# Sheet4.net
KiCad netlist of a schematic drawn in Altium Designer
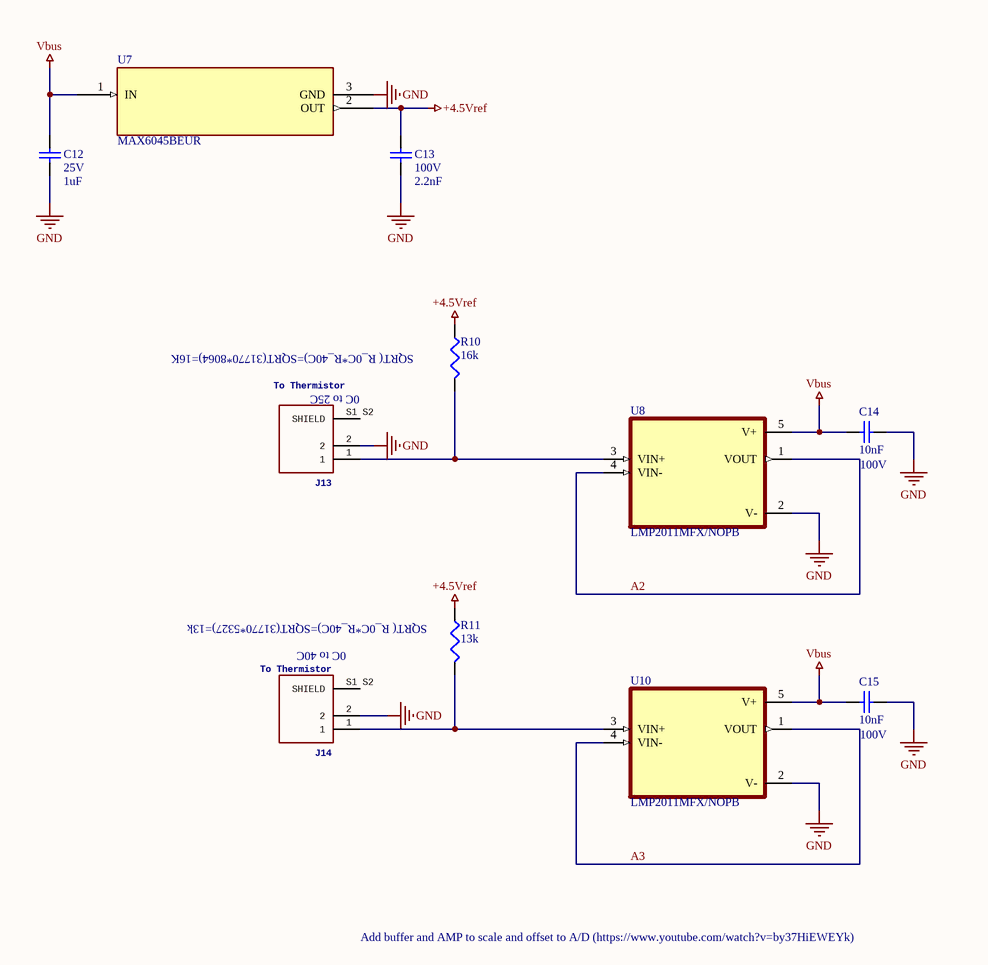
[diagram p0: Sheet4.SchDoc]

(export (version "E")
  (design (tool "Eeschema 10.0.6"))
  (components
    (comp (ref "C12")
      (value "25V")
      (footprint "1608[0603]")
      (description "CAP CER 1UF 25V X7R 0603")
      (fields
        (field (name "ALTIUM_VALUE") "1uF")
        (field (name "MANUFACTURER PART #") "AC0603KRX7R8BB105")
        (field (name "MANUFACTURER") "YAGEO")
      )
      (libsource (lib "Miscellaneous Devices") (part "Cap Semi"))
    )
    (comp (ref "C13")
      (value "100V")
      (footprint "1608[0603]")
      (description "CAP CER 2200PF 100V X7R 0603")
      (fields
        (field (name "ALTIUM_VALUE") "2.2nF")
        (field (name "MANUFACTURER PART #") "CC0603KRX7R0BB222")
        (field (name "MANUFACTURER") "YAGEO")
      )
      (libsource (lib "Miscellaneous Devices") (part "Cap Semi"))
    )
    (comp (ref "C14")
      (value "100V")
      (footprint "1608[0603]")
      (description "CAP CER 10000PF 100V X7R 0603")
      (fields
        (field (name "ALTIUM_VALUE") "10nF")
        (field (name "MANUFACTURER") "YAGEO")
        (field (name "MANUFACTURER PART #") "CC0603KRX7R0BB103")
      )
      (libsource (lib "Miscellaneous Devices") (part "Cap Semi"))
    )
    (comp (ref "C15")
      (value "100V")
      (footprint "1608[0603]")
      (description "CAP CER 10000PF 100V X7R 0603")
      (fields
        (field (name "ALTIUM_VALUE") "10nF")
        (field (name "MANUFACTURER") "YAGEO")
        (field (name "MANUFACTURER PART #") "CC0603KRX7R0BB103")
      )
      (libsource (lib "Miscellaneous Devices") (part "Cap Semi"))
    )
    (comp (ref "J13")
      (value "To Thermistor")
      (footprint "CONN_BM04B-SRSS-TB(LF)(SN)")
      (fields
        (field (name "MANUFACTURER") "JST Sales")
        (field (name "MANUFACTURER PART #") "BM04B-SRSS-TB(LF)(SN)")
      )
      (libsource (lib "BM02B-SRSS-TB_LF__SN_") (part "BM04B-SRSS-TB(LF)(SN)"))
    )
    (comp (ref "J14")
      (value "To Thermistor")
      (footprint "CONN_BM04B-SRSS-TB(LF)(SN)")
      (fields
        (field (name "MANUFACTURER") "JST Sales")
        (field (name "MANUFACTURER PART #") "BM04B-SRSS-TB(LF)(SN)")
      )
      (libsource (lib "BM02B-SRSS-TB_LF__SN_") (part "BM04B-SRSS-TB(LF)(SN)"))
    )
    (comp (ref "R10")
      (value "16k")
      (footprint "J1-0603")
      (description "Resistor, 0.1%, 1/10W")
      (fields
        (field (name "MANUFACTURER PART #") "ERA-3AEB163V")
        (field (name "MANUFACTURER") "Panasonic Electronic Components")
      )
      (libsource (lib "Miscellaneous Devices") (part "Res3"))
    )
    (comp (ref "R11")
      (value "13k")
      (footprint "J1-0603")
      (description "Resistor, 0.1%, 1/5W")
      (fields
        (field (name "MANUFACTURER PART #") "ERJ-PB3B1302V")
        (field (name "MANUFACTURER") "Panasonic Electronic Components")
      )
      (libsource (lib "Miscellaneous Devices") (part "Res3"))
    )
    (comp (ref "U7")
      (value "MAX6045BEUR")
      (footprint "21-0051H")
      (description "Voltage References Precision, Low-Power, Low-Dropout, SOT23-3 Voltage References")
      (fields (field (name "MANUFACTURER") "Analog Devices Inc./Maxim Integrated"))
      (libsource (lib "MAX6045AEUR") (part "MAX6045AEUR"))
    )
    (comp (ref "U8")
      (value "LMP2011MFX/NOPB")
      (footprint "SOT95P280X145-5N")
      (description "Single, High Precision, Rail-to-Rail Output Operational Amplifier")
      (fields (field (name "MANUFACTURER") "Texas Instruments"))
      (libsource (lib "LMP2011MFX_NOPB") (part "LMP2011MFX/NOPB"))
    )
    (comp (ref "U10")
      (value "LMP2011MFX/NOPB")
      (description "Single, High Precision, Rail-to-Rail Output Operational Amplifier")
      (fields (field (name "MANUFACTURER") "Texas Instruments"))
      (libsource (lib "LMP2011MFX_NOPB") (part "LMP2011MFX/NOPB"))
    )
  )
  (nets
    (net (code "1") (name "+4.5Vref") (class "Default")
      (node (ref "C13") (pin "2") (pinfunction "2_2") (pintype "passive"))
      (node (ref "R10") (pin "1") (pinfunction "1_1") (pintype "passive"))
      (node (ref "R11") (pin "1") (pinfunction "1_1") (pintype "passive"))
      (node (ref "U7") (pin "2") (pinfunction "OUT_2") (pintype "output"))
    )
    (net (code "2") (name "/A2") (class "Default")
      (node (ref "U8") (pin "1") (pinfunction "VOUT_1") (pintype "output"))
      (node (ref "U8") (pin "4") (pinfunction "VIN-_4") (pintype "input"))
    )
    (net (code "3") (name "/A3") (class "Default")
      (node (ref "U10") (pin "1") (pinfunction "VOUT_1") (pintype "output"))
      (node (ref "U10") (pin "4") (pinfunction "VIN-_4") (pintype "input"))
    )
    (net (code "4") (name "GND") (class "Default")
      (node (ref "C12") (pin "1") (pinfunction "1_1") (pintype "passive"))
      (node (ref "C13") (pin "1") (pinfunction "1_1") (pintype "passive"))
      (node (ref "C14") (pin "1") (pinfunction "1_1") (pintype "passive"))
      (node (ref "C15") (pin "1") (pinfunction "1_1") (pintype "passive"))
      (node (ref "J13") (pin "2") (pinfunction "2_2") (pintype "passive"))
      (node (ref "J14") (pin "2") (pinfunction "2_2") (pintype "passive"))
      (node (ref "U10") (pin "2") (pinfunction "V-_2") (pintype "power_in"))
      (node (ref "U7") (pin "3") (pinfunction "GND_3") (pintype "power_in"))
      (node (ref "U8") (pin "2") (pinfunction "V-_2") (pintype "power_in"))
    )
    (net (code "5") (name "Net-(U8-VIN+)") (class "Default")
      (node (ref "J13") (pin "1") (pinfunction "1_1") (pintype "passive"))
      (node (ref "R10") (pin "2") (pinfunction "2_2") (pintype "passive"))
      (node (ref "U8") (pin "3") (pinfunction "VIN+_3") (pintype "input"))
    )
    (net (code "6") (name "Net-(U10-VIN+)") (class "Default")
      (node (ref "J14") (pin "1") (pinfunction "1_1") (pintype "passive"))
      (node (ref "R11") (pin "2") (pinfunction "2_2") (pintype "passive"))
      (node (ref "U10") (pin "3") (pinfunction "VIN+_3") (pintype "input"))
    )
    (net (code "7") (name "Vbus") (class "Default")
      (node (ref "C12") (pin "2") (pinfunction "2_2") (pintype "passive"))
      (node (ref "C14") (pin "2") (pinfunction "2_2") (pintype "passive"))
      (node (ref "C15") (pin "2") (pinfunction "2_2") (pintype "passive"))
      (node (ref "U10") (pin "5") (pinfunction "V+_5") (pintype "power_in"))
      (node (ref "U7") (pin "1") (pinfunction "IN_1") (pintype "input"))
      (node (ref "U8") (pin "5") (pinfunction "V+_5") (pintype "power_in"))
    )
    (net (code "8") (name "unconnected-(J13-SHIELD-PadS1_S2)") (class "Default")
      (node (ref "J13") (pin "S1_S2") (pinfunction "SHIELD_S1_S2") (pintype "passive"))
    )
    (net (code "9") (name "unconnected-(J14-SHIELD-PadS1_S2)") (class "Default")
      (node (ref "J14") (pin "S1_S2") (pinfunction "SHIELD_S1_S2") (pintype "passive"))
    )
  )
)
